# PROK_drum_B.net
KiCad netlist of a schematic drawn in EAGLE
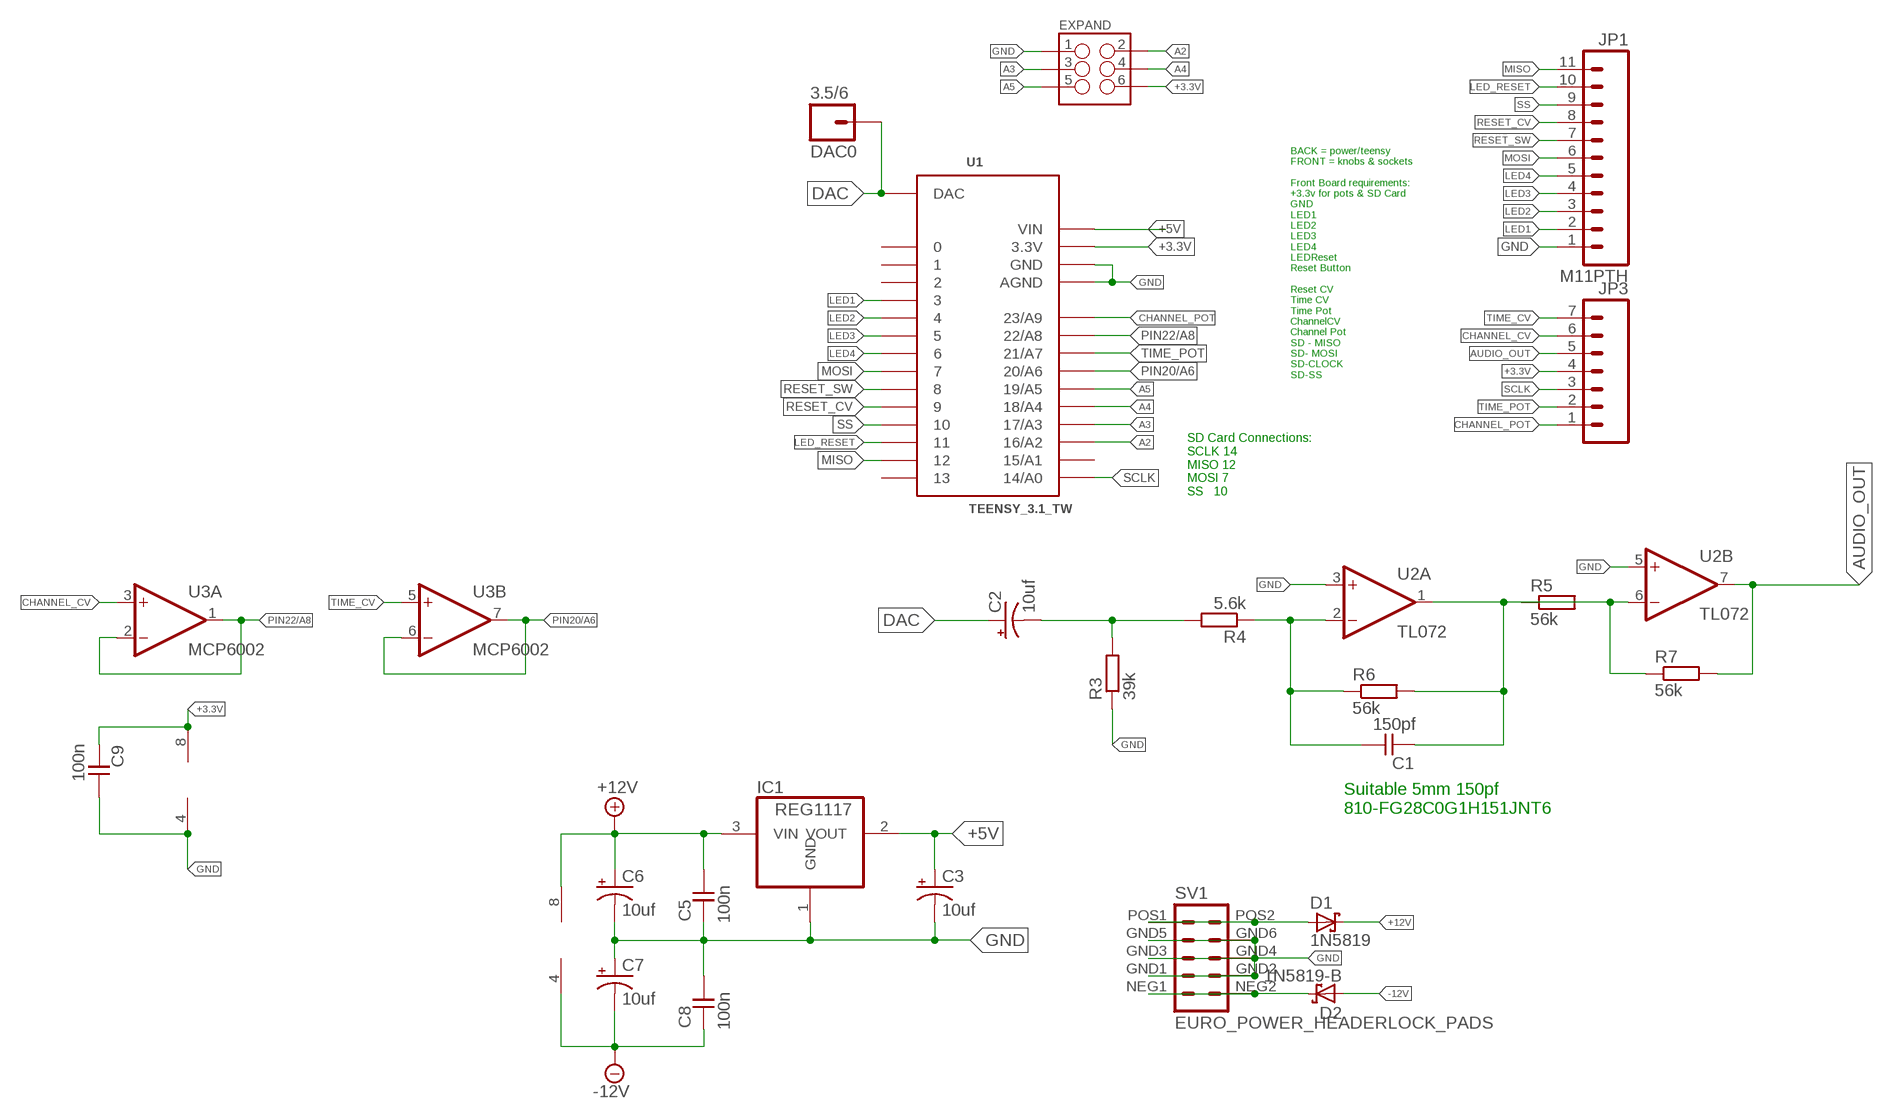
[diagram p0: schematic, sheet 1]

(export (version "E")
  (design (tool "Eeschema 10.0.6"))
  (components
    (comp (ref "3.5/6")
      (value "DAC0")
      (footprint "eagle-import:1X01")
      (libsource (lib "eagle-import") (part "M01PTH"))
    )
    (comp (ref "C1")
      (value "150pf")
      (footprint "eagle-import:C050-024X044")
      (libsource (lib "eagle-import") (part "C-EU050-024X044"))
    )
    (comp (ref "C2")
      (value "10uf")
      (footprint "eagle-import:CPOL-RADIAL-10UF-25V")
      (libsource (lib "eagle-import") (part "CAP_POLPTH2"))
    )
    (comp (ref "C3")
      (value "10uf")
      (footprint "eagle-import:CPOL-RADIAL-10UF-25V")
      (libsource (lib "eagle-import") (part "CAP_POLPTH2"))
    )
    (comp (ref "C5")
      (value "100n")
      (footprint "eagle-import:C050-024X044")
      (libsource (lib "eagle-import") (part "C-EU050-024X044"))
    )
    (comp (ref "C6")
      (value "10uf")
      (footprint "eagle-import:CPOL-RADIAL-10UF-25V")
      (libsource (lib "eagle-import") (part "CAP_POLPTH2"))
    )
    (comp (ref "C7")
      (value "10uf")
      (footprint "eagle-import:CPOL-RADIAL-10UF-25V")
      (libsource (lib "eagle-import") (part "CAP_POLPTH2"))
    )
    (comp (ref "C8")
      (value "100n")
      (footprint "eagle-import:C050-024X044")
      (libsource (lib "eagle-import") (part "C-EU050-024X044"))
    )
    (comp (ref "C9")
      (value "100n")
      (footprint "eagle-import:C050-024X044")
      (libsource (lib "eagle-import") (part "C-EU050-024X044"))
    )
    (comp (ref "D1")
      (value "1N5819")
      (footprint "eagle-import:DO41-7.6")
      (libsource (lib "eagle-import") (part "1N5819-B"))
    )
    (comp (ref "D2")
      (value "1N5819-B")
      (footprint "eagle-import:DO41-7.6")
      (libsource (lib "eagle-import") (part "1N5819-B"))
    )
    (comp (ref "EXPAND")
      (value "M03X22X3_SILK_SM")
      (footprint "eagle-import:2X3")
      (libsource (lib "eagle-import") (part "M03X22X3_SILK_SM"))
    )
    (comp (ref "IC1")
      (value "REG1117")
      (footprint "eagle-import:SOT223")
      (libsource (lib "eagle-import") (part "REG1117"))
    )
    (comp (ref "JP1")
      (value "M11PTH")
      (footprint "eagle-import:1X11")
      (libsource (lib "eagle-import") (part "M11PTH"))
    )
    (comp (ref "JP3")
      (value "M07")
      (footprint "eagle-import:1X07")
      (libsource (lib "eagle-import") (part "M07"))
    )
    (comp (ref "R3")
      (value "39k")
      (footprint "eagle-import:7MM_RESISTOR")
      (libsource (lib "eagle-import") (part "RESISTOR7MM"))
    )
    (comp (ref "R4")
      (value "5.6k")
      (footprint "eagle-import:7MM_RESISTOR")
      (libsource (lib "eagle-import") (part "RESISTOR7MM"))
    )
    (comp (ref "R5")
      (value "56k")
      (footprint "eagle-import:7MM_RESISTOR")
      (libsource (lib "eagle-import") (part "RESISTOR7MM"))
    )
    (comp (ref "R6")
      (value "56k")
      (footprint "eagle-import:7MM_RESISTOR")
      (libsource (lib "eagle-import") (part "RESISTOR7MM"))
    )
    (comp (ref "R7")
      (value "56k")
      (footprint "eagle-import:7MM_RESISTOR")
      (libsource (lib "eagle-import") (part "RESISTOR7MM"))
    )
    (comp (ref "SV1")
      (value "EURO_POWER_HEADERLOCK_PADS")
      (footprint "eagle-import:EURO_PWR_HEADER_LOCK")
      (libsource (lib "eagle-import") (part "EURO_POWER_HEADERLOCK_PADS"))
    )
    (comp (ref "U1")
      (value "TEENSY_3.1_TW")
      (footprint "eagle-import:TEENSY_3.1_TW")
      (libsource (lib "eagle-import") (part "TEENSY_3.1_TW"))
    )
    (comp (ref "U2")
      (value "TL072")
      (footprint "eagle-import:DIL08-SML")
      (libsource (lib "eagle-import") (part "TL072"))
    )
    (comp (ref "U3")
      (value "MCP6002")
      (footprint "eagle-import:DIL08-SML")
      (libsource (lib "eagle-import") (part "MCP6002DIL_SMALL"))
    )
  )
  (nets
    (net (code "1") (name "+3.3V") (class "Default")
      (node (ref "C9") (pin "2") (pinfunction "2_2") (pintype "passive"))
      (node (ref "EXPAND") (pin "6") (pinfunction "6_6") (pintype "bidirectional"))
      (node (ref "JP3") (pin "4") (pinfunction "4_4") (pintype "passive"))
      (node (ref "U1") (pin "3.3V") (pinfunction "3.3V_3.3V") (pintype "power_in"))
      (node (ref "U3") (pin "8") (pinfunction "V+_8") (pintype "power_in"))
    )
    (net (code "2") (name "+5V") (class "Default")
      (node (ref "C3") (pin "1") (pinfunction "+_1") (pintype "passive"))
      (node (ref "IC1") (pin "2") (pinfunction "VOUT_2") (pintype "output"))
      (node (ref "U1") (pin "VIN") (pinfunction "VIN_VIN") (pintype "power_in"))
    )
    (net (code "3") (name "+12V") (class "Default")
      (node (ref "C5") (pin "1") (pinfunction "1_1") (pintype "passive"))
      (node (ref "C6") (pin "1") (pinfunction "+_1") (pintype "passive"))
      (node (ref "D1") (pin "C") (pinfunction "C_C") (pintype "passive"))
      (node (ref "IC1") (pin "3") (pinfunction "VIN_3") (pintype "input"))
      (node (ref "U2") (pin "8") (pinfunction "V+_8") (pintype "power_in"))
    )
    (net (code "4") (name "-12V") (class "Default")
      (node (ref "C7") (pin "2") (pinfunction "-_2") (pintype "passive"))
      (node (ref "C8") (pin "2") (pinfunction "2_2") (pintype "passive"))
      (node (ref "D2") (pin "A") (pinfunction "A_A") (pintype "passive"))
      (node (ref "U2") (pin "4") (pinfunction "V-_4") (pintype "power_in"))
    )
    (net (code "5") (name "A2") (class "Default")
      (node (ref "EXPAND") (pin "2") (pinfunction "2_2") (pintype "bidirectional"))
      (node (ref "U1") (pin "16/A2") (pinfunction "16/A2_16/A2") (pintype "bidirectional"))
    )
    (net (code "6") (name "A3") (class "Default")
      (node (ref "EXPAND") (pin "3") (pinfunction "3_3") (pintype "bidirectional"))
      (node (ref "U1") (pin "17/A3") (pinfunction "17/A3_17/A3") (pintype "bidirectional"))
    )
    (net (code "7") (name "A4") (class "Default")
      (node (ref "EXPAND") (pin "4") (pinfunction "4_4") (pintype "bidirectional"))
      (node (ref "U1") (pin "18/A4") (pinfunction "18/A4_18/A4") (pintype "bidirectional"))
    )
    (net (code "8") (name "A5") (class "Default")
      (node (ref "EXPAND") (pin "5") (pinfunction "5_5") (pintype "bidirectional"))
      (node (ref "U1") (pin "19/A5") (pinfunction "19/A5_19/A5") (pintype "bidirectional"))
    )
    (net (code "9") (name "AUDIO_OUT") (class "Default")
      (node (ref "JP3") (pin "5") (pinfunction "5_5") (pintype "passive"))
      (node (ref "R7") (pin "2") (pinfunction "2_2") (pintype "passive"))
      (node (ref "U2") (pin "7") (pinfunction "OUT_7") (pintype "output"))
    )
    (net (code "10") (name "CHANNEL_CV") (class "Default")
      (node (ref "JP3") (pin "6") (pinfunction "6_6") (pintype "passive"))
      (node (ref "U3") (pin "3") (pinfunction "+IN_3") (pintype "input"))
    )
    (net (code "11") (name "CHANNEL_POT") (class "Default")
      (node (ref "JP3") (pin "1") (pinfunction "1_1") (pintype "passive"))
      (node (ref "U1") (pin "23/A9") (pinfunction "23/A9_23/A9") (pintype "bidirectional"))
    )
    (net (code "12") (name "DAC") (class "Default")
      (node (ref "3.5/6") (pin "1") (pinfunction "1_1") (pintype "passive"))
      (node (ref "C2") (pin "1") (pinfunction "+_1") (pintype "passive"))
      (node (ref "U1") (pin "DAC") (pinfunction "DAC_DAC") (pintype "bidirectional"))
    )
    (net (code "13") (name "GND") (class "Default")
      (node (ref "C3") (pin "2") (pinfunction "-_2") (pintype "passive"))
      (node (ref "C5") (pin "2") (pinfunction "2_2") (pintype "passive"))
      (node (ref "C6") (pin "2") (pinfunction "-_2") (pintype "passive"))
      (node (ref "C7") (pin "1") (pinfunction "+_1") (pintype "passive"))
      (node (ref "C8") (pin "1") (pinfunction "1_1") (pintype "passive"))
      (node (ref "C9") (pin "1") (pinfunction "1_1") (pintype "passive"))
      (node (ref "EXPAND") (pin "1") (pinfunction "1_1") (pintype "bidirectional"))
      (node (ref "IC1") (pin "1") (pinfunction "GND_1") (pintype "power_in"))
      (node (ref "JP1") (pin "1") (pinfunction "1_1") (pintype "passive"))
      (node (ref "R3") (pin "1") (pinfunction "1_1") (pintype "passive"))
      (node (ref "SV1") (pin "GND1") (pinfunction "4_GND1") (pintype "passive"))
      (node (ref "SV1") (pin "GND2") (pinfunction "3_GND2") (pintype "passive"))
      (node (ref "SV1") (pin "GND3") (pinfunction "6_GND3") (pintype "passive"))
      (node (ref "SV1") (pin "GND4") (pinfunction "5_GND4") (pintype "passive"))
      (node (ref "SV1") (pin "GND5") (pinfunction "8_GND5") (pintype "passive"))
      (node (ref "SV1") (pin "GND6") (pinfunction "7_GND6") (pintype "passive"))
      (node (ref "U1") (pin "AGND") (pinfunction "AGND_AGND") (pintype "power_in"))
      (node (ref "U1") (pin "GND") (pinfunction "GND_GND") (pintype "power_in"))
      (node (ref "U2") (pin "3") (pinfunction "+IN_3") (pintype "input"))
      (node (ref "U2") (pin "5") (pinfunction "+IN_5") (pintype "input"))
      (node (ref "U3") (pin "4") (pinfunction "V-_4") (pintype "power_in"))
    )
    (net (code "14") (name "LED1") (class "Default")
      (node (ref "JP1") (pin "2") (pinfunction "2_2") (pintype "passive"))
      (node (ref "U1") (pin "3") (pinfunction "3_3") (pintype "bidirectional"))
    )
    (net (code "15") (name "LED2") (class "Default")
      (node (ref "JP1") (pin "3") (pinfunction "3_3") (pintype "passive"))
      (node (ref "U1") (pin "4") (pinfunction "4_4") (pintype "bidirectional"))
    )
    (net (code "16") (name "LED3") (class "Default")
      (node (ref "JP1") (pin "4") (pinfunction "4_4") (pintype "passive"))
      (node (ref "U1") (pin "5") (pinfunction "5_5") (pintype "bidirectional"))
    )
    (net (code "17") (name "LED4") (class "Default")
      (node (ref "JP1") (pin "5") (pinfunction "5_5") (pintype "passive"))
      (node (ref "U1") (pin "6") (pinfunction "6_6") (pintype "bidirectional"))
    )
    (net (code "18") (name "LED_RESET") (class "Default")
      (node (ref "JP1") (pin "10") (pinfunction "10_10") (pintype "passive"))
      (node (ref "U1") (pin "11") (pinfunction "11_11") (pintype "bidirectional"))
    )
    (net (code "19") (name "MISO") (class "Default")
      (node (ref "JP1") (pin "11") (pinfunction "11_11") (pintype "passive"))
      (node (ref "U1") (pin "12") (pinfunction "12_12") (pintype "bidirectional"))
    )
    (net (code "20") (name "MOSI") (class "Default")
      (node (ref "JP1") (pin "6") (pinfunction "6_6") (pintype "passive"))
      (node (ref "U1") (pin "7") (pinfunction "7_7") (pintype "bidirectional"))
    )
    (net (code "21") (name "Net-(C2--)") (class "Default")
      (node (ref "C2") (pin "2") (pinfunction "-_2") (pintype "passive"))
      (node (ref "R3") (pin "2") (pinfunction "2_2") (pintype "passive"))
      (node (ref "R4") (pin "2") (pinfunction "2_2") (pintype "passive"))
    )
    (net (code "22") (name "Net-(SV1-1)") (class "Default")
      (node (ref "D2") (pin "C") (pinfunction "C_C") (pintype "passive"))
      (node (ref "SV1") (pin "NEG1") (pinfunction "2_NEG1") (pintype "passive"))
      (node (ref "SV1") (pin "NEG2") (pinfunction "1_NEG2") (pintype "passive"))
    )
    (net (code "23") (name "Net-(SV1-10)") (class "Default")
      (node (ref "D1") (pin "A") (pinfunction "A_A") (pintype "passive"))
      (node (ref "SV1") (pin "POS1") (pinfunction "10_POS1") (pintype "passive"))
      (node (ref "SV1") (pin "POS2") (pinfunction "9_POS2") (pintype "passive"))
    )
    (net (code "24") (name "Net-(U2A--IN)") (class "Default")
      (node (ref "C1") (pin "1") (pinfunction "1_1") (pintype "passive"))
      (node (ref "R4") (pin "1") (pinfunction "1_1") (pintype "passive"))
      (node (ref "R6") (pin "1") (pinfunction "1_1") (pintype "passive"))
      (node (ref "U2") (pin "2") (pinfunction "-IN_2") (pintype "input"))
    )
    (net (code "25") (name "Net-(U2A-OUT)") (class "Default")
      (node (ref "C1") (pin "2") (pinfunction "2_2") (pintype "passive"))
      (node (ref "R5") (pin "2") (pinfunction "2_2") (pintype "passive"))
      (node (ref "R6") (pin "2") (pinfunction "2_2") (pintype "passive"))
      (node (ref "U2") (pin "1") (pinfunction "OUT_1") (pintype "output"))
    )
    (net (code "26") (name "Net-(U2B--IN)") (class "Default")
      (node (ref "R5") (pin "1") (pinfunction "1_1") (pintype "passive"))
      (node (ref "R7") (pin "1") (pinfunction "1_1") (pintype "passive"))
      (node (ref "U2") (pin "6") (pinfunction "-IN_6") (pintype "input"))
    )
    (net (code "27") (name "PIN20{slash}A6") (class "Default")
      (node (ref "U1") (pin "20/A6") (pinfunction "20/A6_20/A6") (pintype "bidirectional"))
      (node (ref "U3") (pin "6") (pinfunction "-IN_6") (pintype "input"))
      (node (ref "U3") (pin "7") (pinfunction "OUT_7") (pintype "output"))
    )
    (net (code "28") (name "PIN22{slash}A8") (class "Default")
      (node (ref "U1") (pin "22/A8") (pinfunction "22/A8_22/A8") (pintype "bidirectional"))
      (node (ref "U3") (pin "1") (pinfunction "OUT_1") (pintype "output"))
      (node (ref "U3") (pin "2") (pinfunction "-IN_2") (pintype "input"))
    )
    (net (code "29") (name "RESET_CV") (class "Default")
      (node (ref "JP1") (pin "8") (pinfunction "8_8") (pintype "passive"))
      (node (ref "U1") (pin "9") (pinfunction "9_9") (pintype "bidirectional"))
    )
    (net (code "30") (name "RESET_SW") (class "Default")
      (node (ref "JP1") (pin "7") (pinfunction "7_7") (pintype "passive"))
      (node (ref "U1") (pin "8") (pinfunction "8_8") (pintype "bidirectional"))
    )
    (net (code "31") (name "SCLK") (class "Default")
      (node (ref "JP3") (pin "3") (pinfunction "3_3") (pintype "passive"))
      (node (ref "U1") (pin "14/A0") (pinfunction "14/A0_14/A0") (pintype "bidirectional"))
    )
    (net (code "32") (name "SS") (class "Default")
      (node (ref "JP1") (pin "9") (pinfunction "9_9") (pintype "passive"))
      (node (ref "U1") (pin "10") (pinfunction "10_10") (pintype "bidirectional"))
    )
    (net (code "33") (name "TIME_CV") (class "Default")
      (node (ref "JP3") (pin "7") (pinfunction "7_7") (pintype "passive"))
      (node (ref "U3") (pin "5") (pinfunction "+IN_5") (pintype "input"))
    )
    (net (code "34") (name "TIME_POT") (class "Default")
      (node (ref "JP3") (pin "2") (pinfunction "2_2") (pintype "passive"))
      (node (ref "U1") (pin "21/A7") (pinfunction "21/A7_21/A7") (pintype "bidirectional"))
    )
    (net (code "35") (name "unconnected-(U1-Pad0)") (class "Default")
      (node (ref "U1") (pin "0") (pinfunction "0_0") (pintype "bidirectional"))
    )
    (net (code "36") (name "unconnected-(U1-Pad1)") (class "Default")
      (node (ref "U1") (pin "1") (pinfunction "1_1") (pintype "bidirectional"))
    )
    (net (code "37") (name "unconnected-(U1-Pad2)") (class "Default")
      (node (ref "U1") (pin "2") (pinfunction "2_2") (pintype "bidirectional"))
    )
    (net (code "38") (name "unconnected-(U1-Pad13)") (class "Default")
      (node (ref "U1") (pin "13") (pinfunction "13_13") (pintype "bidirectional"))
    )
    (net (code "39") (name "unconnected-(U1-Pad15{slash}A1)") (class "Default")
      (node (ref "U1") (pin "15/A1") (pinfunction "15/A1_15/A1") (pintype "bidirectional"))
    )
  )
)
